# STATION_1608_v1.net
KiCad netlist of a schematic drawn in EAGLE
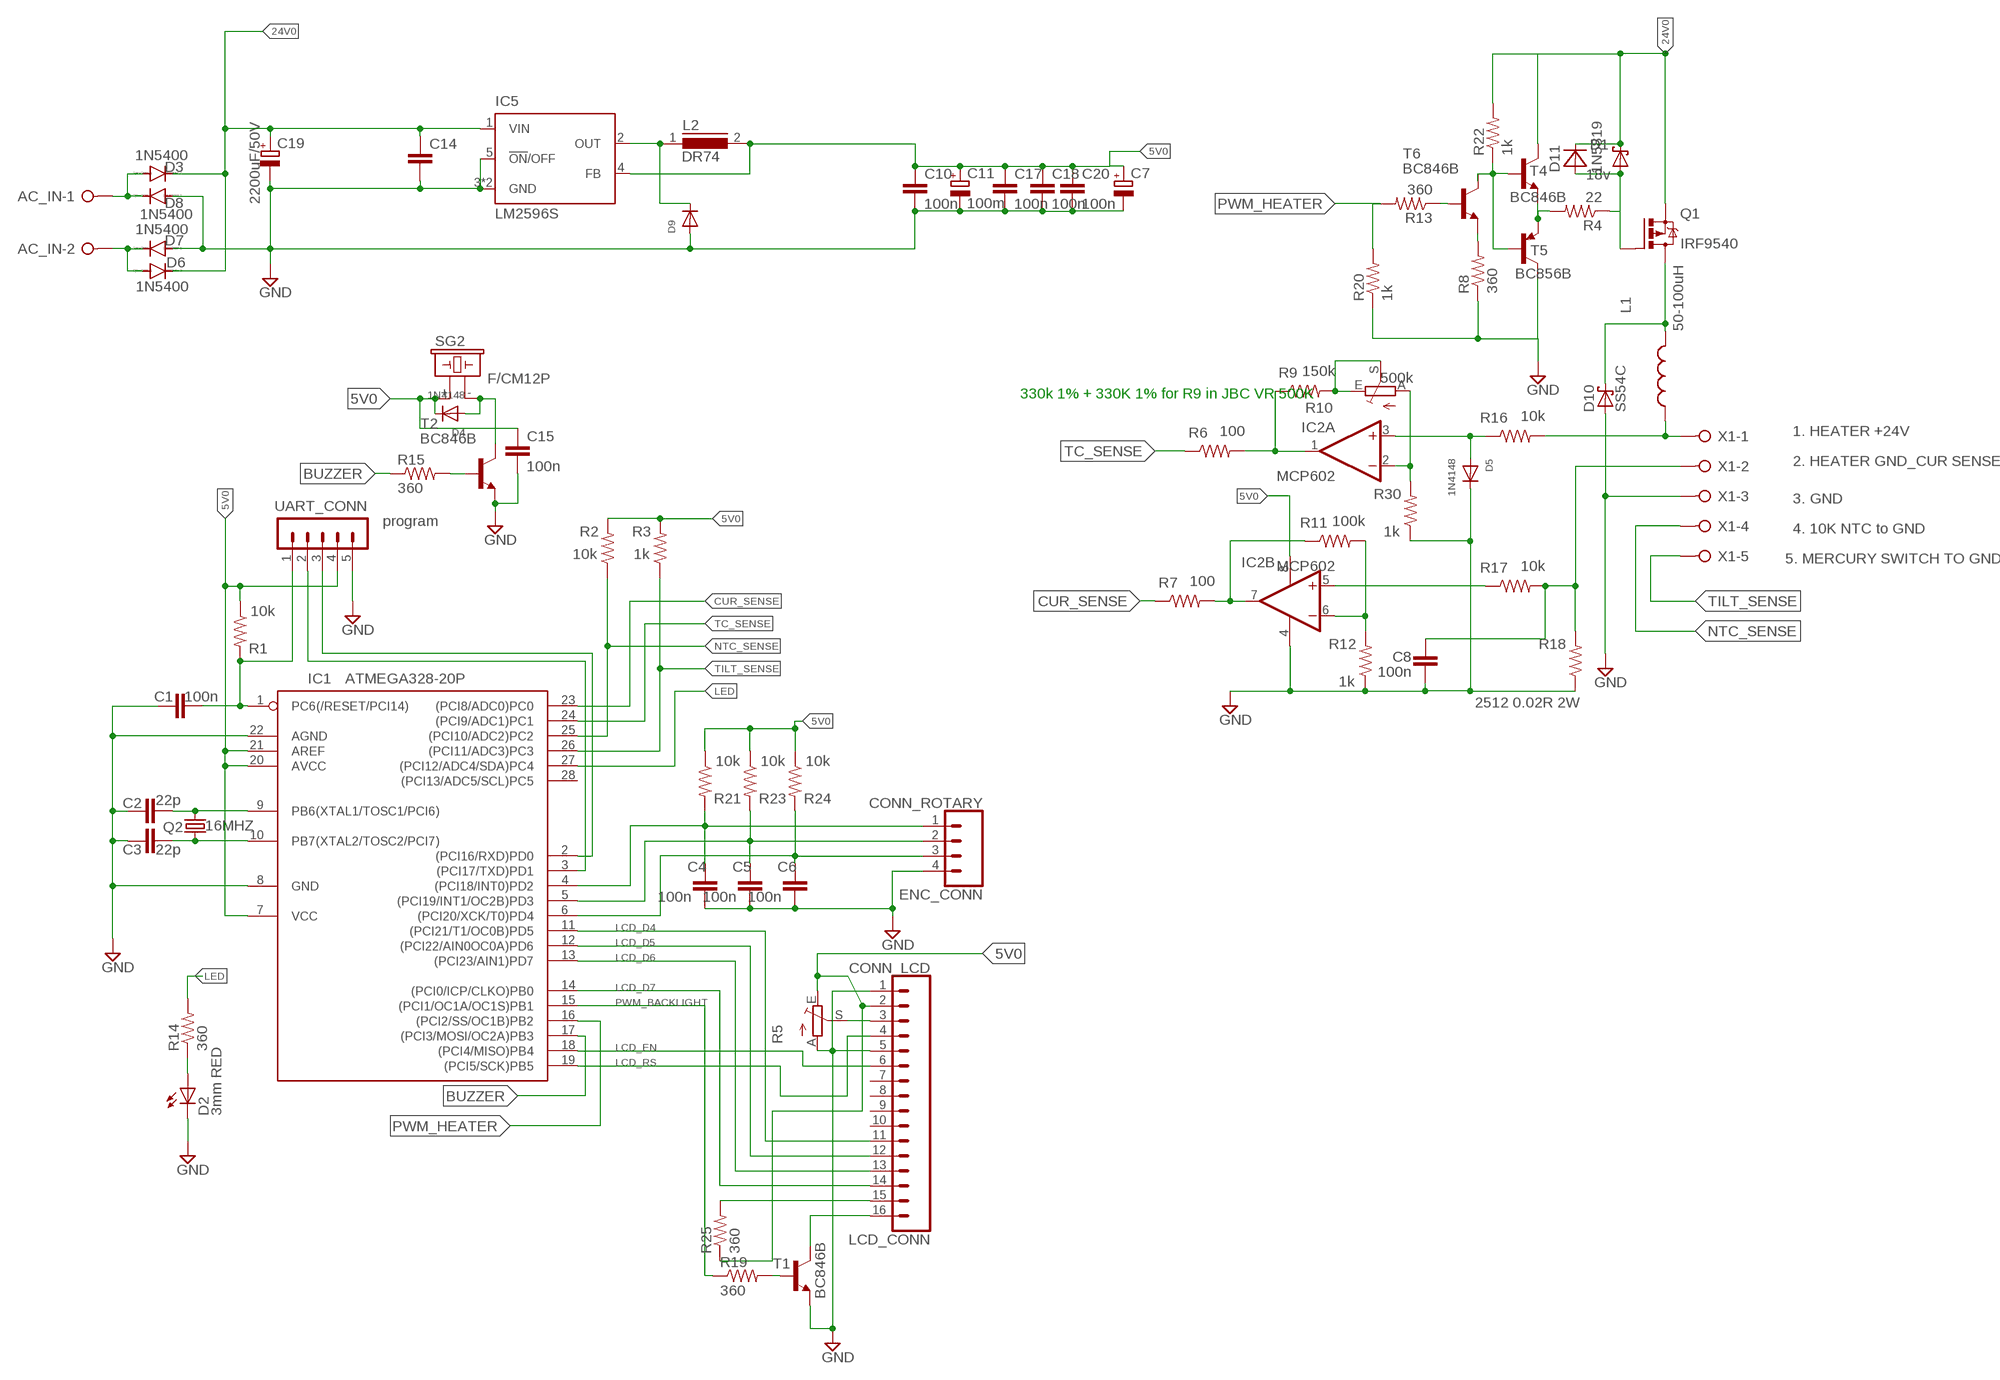
[diagram p0: schematic, sheet 1]

(export (version "E")
  (design (tool "Eeschema 10.0.6"))
  (components
    (comp (ref "AC_IN")
      (value "W237-02P")
      (footprint "eagle-import:W237-132")
      (libsource (lib "eagle-import") (part "W237-02P"))
    )
    (comp (ref "C1")
      (value "100n")
      (footprint "eagle-import:C0805")
      (libsource (lib "eagle-import") (part "C-EUC0805"))
    )
    (comp (ref "C2")
      (value "22p")
      (footprint "eagle-import:C0805")
      (libsource (lib "eagle-import") (part "C-EUC0805"))
    )
    (comp (ref "C3")
      (value "22p")
      (footprint "eagle-import:C0805")
      (libsource (lib "eagle-import") (part "C-EUC0805"))
    )
    (comp (ref "C4")
      (value "100n")
      (footprint "eagle-import:C0805")
      (libsource (lib "eagle-import") (part "C-EUC0805"))
    )
    (comp (ref "C5")
      (value "100n")
      (footprint "eagle-import:C0805")
      (libsource (lib "eagle-import") (part "C-EUC0805"))
    )
    (comp (ref "C6")
      (value "100n")
      (footprint "eagle-import:C0805")
      (libsource (lib "eagle-import") (part "C-EUC0805"))
    )
    (comp (ref "C7")
      (value "CPOL-EUE3.5-8")
      (footprint "eagle-import:E3,5-8")
      (libsource (lib "eagle-import") (part "CPOL-EUE3.5-8"))
    )
    (comp (ref "C8")
      (value "100n")
      (footprint "eagle-import:C0805")
      (libsource (lib "eagle-import") (part "C-EUC0805"))
    )
    (comp (ref "C10")
      (value "100n")
      (footprint "eagle-import:C0805")
      (libsource (lib "eagle-import") (part "resistor_C-EUC0805"))
    )
    (comp (ref "C11")
      (value "100m")
      (footprint "eagle-import:E3,5-8")
      (libsource (lib "eagle-import") (part "CPOL-EUE3.5-8"))
    )
    (comp (ref "C14")
      (value "100n")
      (footprint "eagle-import:C0805")
      (libsource (lib "eagle-import") (part "resistor_C-EUC0805"))
    )
    (comp (ref "C15")
      (value "100n")
      (footprint "eagle-import:C0805K")
      (libsource (lib "eagle-import") (part "C-EUC0805K"))
    )
    (comp (ref "C17")
      (value "100n")
      (footprint "eagle-import:C0805")
      (libsource (lib "eagle-import") (part "resistor_C-EUC0805"))
    )
    (comp (ref "C18")
      (value "100n")
      (footprint "eagle-import:C0805")
      (libsource (lib "eagle-import") (part "resistor_C-EUC0805"))
    )
    (comp (ref "C19")
      (value "2200uF/50V")
      (footprint "eagle-import:E7,5-16")
      (libsource (lib "eagle-import") (part "CPOL-EUE7.5-16"))
    )
    (comp (ref "C20")
      (value "100n")
      (footprint "eagle-import:C0805")
      (libsource (lib "eagle-import") (part "resistor_C-EUC0805"))
    )
    (comp (ref "D1")
      (value "18v")
      (footprint "eagle-import:SOD80C")
      (libsource (lib "eagle-import") (part "BAS85"))
    )
    (comp (ref "D2")
      (value "3mm RED")
      (footprint "eagle-import:LED5MM")
      (libsource (lib "eagle-import") (part "LED5MM"))
    )
    (comp (ref "D3")
      (value "1N5400")
      (footprint "eagle-import:DO201-15")
      (libsource (lib "eagle-import") (part "1N5400"))
    )
    (comp (ref "D4")
      (value "1N4148")
      (footprint "eagle-import:SOD-123")
      (libsource (lib "eagle-import") (part "DIODESOD-123"))
    )
    (comp (ref "D5")
      (value "1N4148")
      (footprint "eagle-import:SOD-123")
      (libsource (lib "eagle-import") (part "DIODESOD-123"))
    )
    (comp (ref "D6")
      (value "1N5400")
      (footprint "eagle-import:DO201-15")
      (libsource (lib "eagle-import") (part "1N5400"))
    )
    (comp (ref "D7")
      (value "1N5400")
      (footprint "eagle-import:DO201-15")
      (libsource (lib "eagle-import") (part "1N5400"))
    )
    (comp (ref "D8")
      (value "1N5400")
      (footprint "eagle-import:DO201-15")
      (libsource (lib "eagle-import") (part "1N5400"))
    )
    (comp (ref "D9")
      (value "DIODESMA")
      (footprint "eagle-import:SMADIODE")
      (libsource (lib "eagle-import") (part "DIODESMA"))
    )
    (comp (ref "D10")
      (value "SS54C")
      (footprint "eagle-import:SMC")
      (libsource (lib "eagle-import") (part "MBRS30T32"))
    )
    (comp (ref "D11")
      (value "1N5819")
      (footprint "eagle-import:SMA")
      (libsource (lib "eagle-import") (part "MBRA340T3"))
    )
    (comp (ref "ENC_CONN")
      (value "CONN_ROTARY")
      (footprint "eagle-import:1X04_LONGPADS")
      (libsource (lib "eagle-import") (part "CONN_04LONGPADS"))
    )
    (comp (ref "IC1")
      (value "ATMEGA328-20P")
      (footprint "eagle-import:DIL28-3")
      (libsource (lib "eagle-import") (part "ATMEGA328P-20"))
    )
    (comp (ref "IC2")
      (value "MCP602")
      (footprint "eagle-import:DIL08")
      (libsource (lib "eagle-import") (part "MCP602P"))
    )
    (comp (ref "IC5")
      (value "LM2596S")
      (footprint "eagle-import:TO263-5")
      (fields (field (name "MF") "NATIONAL SEMICONDUCTOR") (field (name "MPN") "LM2596S-ADJ/NOPB"))
      (libsource (lib "eagle-import") (part "LM2596S"))
    )
    (comp (ref "L1")
      (value "50-100uH")
      (footprint "eagle-import:IRF46")
      (libsource (lib "eagle-import") (part "L-USIRF-46"))
    )
    (comp (ref "L2")
      (value "DR74")
      (footprint "eagle-import:DR74")
      (libsource (lib "eagle-import") (part "DR74"))
    )
    (comp (ref "LCD_CONN")
      (value "CONN_LCD")
      (footprint "eagle-import:1X16_LONGPADS")
      (libsource (lib "eagle-import") (part "CONN_16LONGPADS"))
    )
    (comp (ref "Q1")
      (value "IRF9540")
      (footprint "eagle-import:TO220BV")
      (libsource (lib "eagle-import") (part "IRF4905FG"))
    )
    (comp (ref "Q2")
      (value "16MHZ")
      (footprint "eagle-import:HC49_S")
      (libsource (lib "eagle-import") (part "CRYSTALHC49S"))
    )
    (comp (ref "R1")
      (value "10k")
      (footprint "eagle-import:M0805")
      (libsource (lib "eagle-import") (part "R-US_M0805"))
    )
    (comp (ref "R2")
      (value "10k")
      (footprint "eagle-import:M0805")
      (libsource (lib "eagle-import") (part "R-US_M0805"))
    )
    (comp (ref "R3")
      (value "1k")
      (footprint "eagle-import:M0805")
      (libsource (lib "eagle-import") (part "R-US_M0805"))
    )
    (comp (ref "R4")
      (value "22")
      (footprint "eagle-import:M0805")
      (libsource (lib "eagle-import") (part "R-US_M0805"))
    )
    (comp (ref "R5")
      (value "TRIM_EU-RJ9W")
      (footprint "eagle-import:RJ9W")
      (libsource (lib "eagle-import") (part "TRIM_EU-RJ9W"))
    )
    (comp (ref "R6")
      (value "100")
      (footprint "eagle-import:M0805")
      (libsource (lib "eagle-import") (part "R-US_M0805"))
    )
    (comp (ref "R7")
      (value "100")
      (footprint "eagle-import:M0805")
      (libsource (lib "eagle-import") (part "R-US_M0805"))
    )
    (comp (ref "R8")
      (value "360")
      (footprint "eagle-import:M0805")
      (libsource (lib "eagle-import") (part "R-US_M0805"))
    )
    (comp (ref "R9")
      (value "150k")
      (footprint "eagle-import:M0805")
      (libsource (lib "eagle-import") (part "R-US_M0805"))
    )
    (comp (ref "R10")
      (value "500k")
      (footprint "eagle-import:RJ9W")
      (libsource (lib "eagle-import") (part "TRIM_EU-RJ9W"))
    )
    (comp (ref "R11")
      (value "100k")
      (footprint "eagle-import:M0805")
      (libsource (lib "eagle-import") (part "R-US_M0805"))
    )
    (comp (ref "R12")
      (value "1k")
      (footprint "eagle-import:M0805")
      (libsource (lib "eagle-import") (part "R-US_M0805"))
    )
    (comp (ref "R13")
      (value "360")
      (footprint "eagle-import:M0805")
      (libsource (lib "eagle-import") (part "R-US_M0805"))
    )
    (comp (ref "R14")
      (value "360")
      (footprint "eagle-import:M0805")
      (libsource (lib "eagle-import") (part "R-US_M0805"))
    )
    (comp (ref "R15")
      (value "360")
      (footprint "eagle-import:M0805")
      (libsource (lib "eagle-import") (part "R-US_M0805"))
    )
    (comp (ref "R16")
      (value "10k")
      (footprint "eagle-import:M0805")
      (libsource (lib "eagle-import") (part "R-US_M0805"))
    )
    (comp (ref "R17")
      (value "10k")
      (footprint "eagle-import:M0805")
      (libsource (lib "eagle-import") (part "R-US_M0805"))
    )
    (comp (ref "R18")
      (value "2512 0.02R 2W")
      (footprint "eagle-import:R2512")
      (libsource (lib "eagle-import") (part "R-US_R2512"))
    )
    (comp (ref "R19")
      (value "360")
      (footprint "eagle-import:M0805")
      (libsource (lib "eagle-import") (part "R-US_M0805"))
    )
    (comp (ref "R20")
      (value "1k")
      (footprint "eagle-import:M0805")
      (libsource (lib "eagle-import") (part "R-US_M0805"))
    )
    (comp (ref "R21")
      (value "10k")
      (footprint "eagle-import:M0805")
      (libsource (lib "eagle-import") (part "R-US_M0805"))
    )
    (comp (ref "R22")
      (value "1k")
      (footprint "eagle-import:M0805")
      (libsource (lib "eagle-import") (part "R-US_M0805"))
    )
    (comp (ref "R23")
      (value "10k")
      (footprint "eagle-import:M0805")
      (libsource (lib "eagle-import") (part "R-US_M0805"))
    )
    (comp (ref "R24")
      (value "10k")
      (footprint "eagle-import:M0805")
      (libsource (lib "eagle-import") (part "R-US_M0805"))
    )
    (comp (ref "R25")
      (value "360")
      (footprint "eagle-import:M0805")
      (libsource (lib "eagle-import") (part "R-US_M0805"))
    )
    (comp (ref "R30")
      (value "1k")
      (footprint "eagle-import:M0805")
      (libsource (lib "eagle-import") (part "R-US_M0805"))
    )
    (comp (ref "SG2")
      (value "F/CM12P")
      (footprint "eagle-import:F_CM12P")
      (libsource (lib "eagle-import") (part "F/CM12P"))
    )
    (comp (ref "T1")
      (value "BC846B")
      (footprint "eagle-import:SOT23-BEC")
      (libsource (lib "eagle-import") (part "-NPN-SOT23-BECBC846B"))
    )
    (comp (ref "T2")
      (value "BC846B")
      (footprint "eagle-import:SOT23-BEC")
      (libsource (lib "eagle-import") (part "-NPN-SOT23-BECBC846B"))
    )
    (comp (ref "T4")
      (value "BC846B")
      (footprint "eagle-import:SOT23-BEC")
      (libsource (lib "eagle-import") (part "-NPN-SOT23-BECBC846B"))
    )
    (comp (ref "T5")
      (value "BC856B")
      (footprint "eagle-import:SOT23-BEC")
      (libsource (lib "eagle-import") (part "-PNP-SOT23-BECBC856B"))
    )
    (comp (ref "T6")
      (value "BC846B")
      (footprint "eagle-import:SOT23-BEC")
      (libsource (lib "eagle-import") (part "-NPN-SOT23-BECBC846B"))
    )
    (comp (ref "UART_CONN")
      (value "program")
      (footprint "eagle-import:MA05-1")
      (libsource (lib "eagle-import") (part "MA05-1"))
    )
    (comp (ref "X1")
      (value "W237-05P")
      (footprint "eagle-import:W237-5P")
      (libsource (lib "eagle-import") (part "W237-05P"))
    )
  )
  (nets
    (net (code "1") (name "/LCD_D4") (class "Default")
      (node (ref "IC1") (pin "11") (pinfunction "(PCI21/T1/OC0B)PD5_11") (pintype "bidirectional"))
      (node (ref "LCD_CONN") (pin "11") (pinfunction "11_11") (pintype "passive"))
    )
    (net (code "2") (name "/LCD_D5") (class "Default")
      (node (ref "IC1") (pin "12") (pinfunction "(PCI22/AIN0OC0A)PD6_12") (pintype "bidirectional"))
      (node (ref "LCD_CONN") (pin "12") (pinfunction "12_12") (pintype "passive"))
    )
    (net (code "3") (name "/LCD_D6") (class "Default")
      (node (ref "IC1") (pin "13") (pinfunction "(PCI23/AIN1)PD7_13") (pintype "bidirectional"))
      (node (ref "LCD_CONN") (pin "13") (pinfunction "13_13") (pintype "passive"))
    )
    (net (code "4") (name "/LCD_D7") (class "Default")
      (node (ref "IC1") (pin "14") (pinfunction "(PCI0/ICP/CLKO)PB0_14") (pintype "bidirectional"))
      (node (ref "LCD_CONN") (pin "14") (pinfunction "14_14") (pintype "passive"))
    )
    (net (code "5") (name "/LCD_EN") (class "Default")
      (node (ref "IC1") (pin "18") (pinfunction "(PCI4/MISO)PB4_18") (pintype "bidirectional"))
      (node (ref "LCD_CONN") (pin "6") (pinfunction "6_6") (pintype "passive"))
    )
    (net (code "6") (name "/LCD_RS") (class "Default")
      (node (ref "IC1") (pin "19") (pinfunction "(PCI5/SCK)PB5_19") (pintype "bidirectional"))
      (node (ref "LCD_CONN") (pin "4") (pinfunction "4_4") (pintype "passive"))
    )
    (net (code "7") (name "/PWM_BACKLIGHT") (class "Default")
      (node (ref "IC1") (pin "15") (pinfunction "(PCI1/OC1A/OC1S)PB1_15") (pintype "bidirectional"))
      (node (ref "R19") (pin "1") (pinfunction "1_1") (pintype "passive"))
    )
    (net (code "8") (name "5V0") (class "Default")
      (node (ref "C10") (pin "1") (pinfunction "1_1") (pintype "passive"))
      (node (ref "C11") (pin "+") (pinfunction "+_+") (pintype "passive"))
      (node (ref "C15") (pin "1") (pinfunction "1_1") (pintype "passive"))
      (node (ref "C17") (pin "1") (pinfunction "1_1") (pintype "passive"))
      (node (ref "C18") (pin "1") (pinfunction "1_1") (pintype "passive"))
      (node (ref "C20") (pin "1") (pinfunction "1_1") (pintype "passive"))
      (node (ref "C7") (pin "+") (pinfunction "+_+") (pintype "passive"))
      (node (ref "D4") (pin "C") (pinfunction "C_C") (pintype "passive"))
      (node (ref "IC1") (pin "20") (pinfunction "AVCC_20") (pintype "bidirectional"))
      (node (ref "IC1") (pin "21") (pinfunction "AREF_21") (pintype "bidirectional"))
      (node (ref "IC1") (pin "7") (pinfunction "VCC_7") (pintype "bidirectional"))
      (node (ref "IC2") (pin "8") (pinfunction "V+_8") (pintype "power_in"))
      (node (ref "IC5") (pin "4") (pinfunction "FB_4") (pintype "input"))
      (node (ref "L2") (pin "2") (pinfunction "2_2") (pintype "passive"))
      (node (ref "LCD_CONN") (pin "2") (pinfunction "2_2") (pintype "passive"))
      (node (ref "R1") (pin "1") (pinfunction "1_1") (pintype "passive"))
      (node (ref "R2") (pin "2") (pinfunction "2_2") (pintype "passive"))
      (node (ref "R21") (pin "1") (pinfunction "1_1") (pintype "passive"))
      (node (ref "R23") (pin "1") (pinfunction "1_1") (pintype "passive"))
      (node (ref "R24") (pin "1") (pinfunction "1_1") (pintype "passive"))
      (node (ref "R25") (pin "1") (pinfunction "1_1") (pintype "passive"))
      (node (ref "R3") (pin "2") (pinfunction "2_2") (pintype "passive"))
      (node (ref "R5") (pin "E") (pinfunction "E_E") (pintype "passive"))
      (node (ref "SG2") (pin "+") (pinfunction "1_+") (pintype "passive"))
      (node (ref "UART_CONN") (pin "4") (pinfunction "4_4") (pintype "passive"))
    )
    (net (code "9") (name "24V0") (class "Default")
      (node (ref "C14") (pin "1") (pinfunction "1_1") (pintype "passive"))
      (node (ref "C19") (pin "+") (pinfunction "+_+") (pintype "passive"))
      (node (ref "D1") (pin "1") (pinfunction "K_1") (pintype "passive"))
      (node (ref "D11") (pin "C") (pinfunction "C_C") (pintype "passive"))
      (node (ref "D3") (pin "C") (pinfunction "C_C") (pintype "passive"))
      (node (ref "D6") (pin "C") (pinfunction "C_C") (pintype "passive"))
      (node (ref "IC5") (pin "1") (pinfunction "VIN_1") (pintype "input"))
      (node (ref "Q1") (pin "S") (pinfunction "S_S") (pintype "passive"))
      (node (ref "R22") (pin "2") (pinfunction "2_2") (pintype "passive"))
      (node (ref "T4") (pin "C") (pinfunction "C_C") (pintype "passive"))
    )
    (net (code "10") (name "BUZZER") (class "Default")
      (node (ref "IC1") (pin "17") (pinfunction "(PCI3/MOSI/OC2A)PB3_17") (pintype "bidirectional"))
      (node (ref "R15") (pin "1") (pinfunction "1_1") (pintype "passive"))
    )
    (net (code "11") (name "CUR_SENSE") (class "Default")
      (node (ref "IC1") (pin "23") (pinfunction "(PCI8/ADC0)PC0_23") (pintype "bidirectional"))
      (node (ref "R7") (pin "1") (pinfunction "1_1") (pintype "passive"))
    )
    (net (code "12") (name "GND") (class "Default")
      (node (ref "C1") (pin "1") (pinfunction "1_1") (pintype "passive"))
      (node (ref "C10") (pin "2") (pinfunction "2_2") (pintype "passive"))
      (node (ref "C11") (pin "-") (pinfunction "-_-") (pintype "passive"))
      (node (ref "C14") (pin "2") (pinfunction "2_2") (pintype "passive"))
      (node (ref "C15") (pin "2") (pinfunction "2_2") (pintype "passive"))
      (node (ref "C17") (pin "2") (pinfunction "2_2") (pintype "passive"))
      (node (ref "C18") (pin "2") (pinfunction "2_2") (pintype "passive"))
      (node (ref "C19") (pin "-") (pinfunction "-_-") (pintype "passive"))
      (node (ref "C2") (pin "1") (pinfunction "1_1") (pintype "passive"))
      (node (ref "C20") (pin "2") (pinfunction "2_2") (pintype "passive"))
      (node (ref "C3") (pin "1") (pinfunction "1_1") (pintype "passive"))
      (node (ref "C4") (pin "2") (pinfunction "2_2") (pintype "passive"))
      (node (ref "C5") (pin "2") (pinfunction "2_2") (pintype "passive"))
      (node (ref "C6") (pin "2") (pinfunction "2_2") (pintype "passive"))
      (node (ref "C7") (pin "-") (pinfunction "-_-") (pintype "passive"))
      (node (ref "C8") (pin "2") (pinfunction "2_2") (pintype "passive"))
      (node (ref "D10") (pin "A") (pinfunction "A_A") (pintype "passive"))
      (node (ref "D2") (pin "K") (pinfunction "C_K") (pintype "passive"))
      (node (ref "D5") (pin "C") (pinfunction "C_C") (pintype "passive"))
      (node (ref "D7") (pin "A") (pinfunction "A_A") (pintype "passive"))
      (node (ref "D8") (pin "A") (pinfunction "A_A") (pintype "passive"))
      (node (ref "D9") (pin "A") (pinfunction "A_A") (pintype "passive"))
      (node (ref "ENC_CONN") (pin "4") (pinfunction "4_4") (pintype "passive"))
      (node (ref "IC1") (pin "22") (pinfunction "AGND_22") (pintype "bidirectional"))
      (node (ref "IC1") (pin "8") (pinfunction "GND_8") (pintype "bidirectional"))
      (node (ref "IC2") (pin "4") (pinfunction "V-_4") (pintype "power_in"))
      (node (ref "IC5") (pin "3") (pinfunction "GND_3") (pintype "power_in"))
      (node (ref "IC5") (pin "5") (pinfunction "~{ON}/OFF_5") (pintype "input"))
      (node (ref "IC5") (pin "6") (pinfunction "GND_6") (pintype "power_in"))
      (node (ref "LCD_CONN") (pin "1") (pinfunction "1_1") (pintype "passive"))
      (node (ref "LCD_CONN") (pin "5") (pinfunction "5_5") (pintype "passive"))
      (node (ref "R12") (pin "1") (pinfunction "1_1") (pintype "passive"))
      (node (ref "R18") (pin "1") (pinfunction "1_1") (pintype "passive"))
      (node (ref "R20") (pin "1") (pinfunction "1_1") (pintype "passive"))
      (node (ref "R30") (pin "1") (pinfunction "1_1") (pintype "passive"))
      (node (ref "R5") (pin "A") (pinfunction "A_A") (pintype "passive"))
      (node (ref "R8") (pin "1") (pinfunction "1_1") (pintype "passive"))
      (node (ref "T1") (pin "E") (pinfunction "E_E") (pintype "passive"))
      (node (ref "T2") (pin "E") (pinfunction "E_E") (pintype "passive"))
      (node (ref "T5") (pin "C") (pinfunction "C_C") (pintype "passive"))
      (node (ref "UART_CONN") (pin "5") (pinfunction "5_5") (pintype "passive"))
      (node (ref "X1") (pin "3") (pinfunction "KL_3") (pintype "passive"))
    )
    (net (code "13") (name "LED") (class "Default")
      (node (ref "IC1") (pin "27") (pinfunction "(PCI12/ADC4/SDA)PC4_27") (pintype "bidirectional"))
      (node (ref "R14") (pin "2") (pinfunction "2_2") (pintype "passive"))
    )
    (net (code "14") (name "NTC_SENSE") (class "Default")
      (node (ref "IC1") (pin "25") (pinfunction "(PCI10/ADC2)PC2_25") (pintype "bidirectional"))
      (node (ref "R2") (pin "1") (pinfunction "1_1") (pintype "passive"))
      (node (ref "X1") (pin "4") (pinfunction "KL_4") (pintype "passive"))
    )
    (net (code "15") (name "Net-(AC_INA-KL)") (class "Default")
      (node (ref "AC_IN") (pin "1") (pinfunction "KL_1") (pintype "passive"))
      (node (ref "D3") (pin "A") (pinfunction "A_A") (pintype "passive"))
      (node (ref "D8") (pin "C") (pinfunction "C_C") (pintype "passive"))
    )
    (net (code "16") (name "Net-(AC_INB-KL)") (class "Default")
      (node (ref "AC_IN") (pin "2") (pinfunction "KL_2") (pintype "passive"))
      (node (ref "D6") (pin "A") (pinfunction "A_A") (pintype "passive"))
      (node (ref "D7") (pin "C") (pinfunction "C_C") (pintype "passive"))
    )
    (net (code "17") (name "Net-(D1-A)") (class "Default")
      (node (ref "D1") (pin "2") (pinfunction "A_2") (pintype "passive"))
      (node (ref "D11") (pin "A") (pinfunction "A_A") (pintype "passive"))
      (node (ref "Q1") (pin "G") (pinfunction "G_G") (pintype "passive"))
      (node (ref "R4") (pin "1") (pinfunction "1_1") (pintype "passive"))
    )
    (net (code "18") (name "Net-(D2-PadA)") (class "Default")
      (node (ref "D2") (pin "A") (pinfunction "A_A") (pintype "passive"))
      (node (ref "R14") (pin "1") (pinfunction "1_1") (pintype "passive"))
    )
    (net (code "19") (name "Net-(D10-PadC)") (class "Default")
      (node (ref "D10") (pin "C") (pinfunction "C_C") (pintype "passive"))
      (node (ref "L1") (pin "2") (pinfunction "2_2") (pintype "passive"))
      (node (ref "Q1") (pin "D") (pinfunction "D_D") (pintype "passive"))
    )
    (net (code "20") (name "Net-(IC1-(PCI16{slash}RXD)PD0)") (class "Default")
      (node (ref "IC1") (pin "2") (pinfunction "(PCI16/RXD)PD0_2") (pintype "bidirectional"))
      (node (ref "UART_CONN") (pin "3") (pinfunction "3_3") (pintype "passive"))
    )
    (net (code "21") (name "Net-(IC1-(PCI17{slash}TXD)PD1)") (class "Default")
      (node (ref "IC1") (pin "3") (pinfunction "(PCI17/TXD)PD1_3") (pintype "bidirectional"))
      (node (ref "UART_CONN") (pin "2") (pinfunction "2_2") (pintype "passive"))
    )
    (net (code "22") (name "Net-(IC1-(PCI18{slash}INT0)PD2)") (class "Default")
      (node (ref "C4") (pin "1") (pinfunction "1_1") (pintype "passive"))
      (node (ref "ENC_CONN") (pin "1") (pinfunction "1_1") (pintype "passive"))
      (node (ref "IC1") (pin "4") (pinfunction "(PCI18/INT0)PD2_4") (pintype "bidirectional"))
      (node (ref "R21") (pin "2") (pinfunction "2_2") (pintype "passive"))
    )
    (net (code "23") (name "Net-(IC1-(PCI19{slash}INT1{slash}OC2B)PD3)") (class "Default")
      (node (ref "C5") (pin "1") (pinfunction "1_1") (pintype "passive"))
      (node (ref "ENC_CONN") (pin "2") (pinfunction "2_2") (pintype "passive"))
      (node (ref "IC1") (pin "5") (pinfunction "(PCI19/INT1/OC2B)PD3_5") (pintype "bidirectional"))
      (node (ref "R23") (pin "2") (pinfunction "2_2") (pintype "passive"))
    )
    (net (code "24") (name "Net-(IC1-(PCI20{slash}XCK{slash}T0)PD4)") (class "Default")
      (node (ref "C6") (pin "1") (pinfunction "1_1") (pintype "passive"))
      (node (ref "ENC_CONN") (pin "3") (pinfunction "3_3") (pintype "passive"))
      (node (ref "IC1") (pin "6") (pinfunction "(PCI20/XCK/T0)PD4_6") (pintype "bidirectional"))
      (node (ref "R24") (pin "2") (pinfunction "2_2") (pintype "passive"))
    )
    (net (code "25") (name "Net-(IC1-PB6(XTAL1{slash}TOSC1{slash}PCI6))") (class "Default")
      (node (ref "C2") (pin "2") (pinfunction "2_2") (pintype "passive"))
      (node (ref "IC1") (pin "9") (pinfunction "PB6(XTAL1/TOSC1/PCI6)_9") (pintype "bidirectional"))
      (node (ref "Q2") (pin "2") (pinfunction "2_2") (pintype "passive"))
    )
    (net (code "26") (name "Net-(IC1-PB7(XTAL2{slash}TOSC2{slash}PCI7))") (class "Default")
      (node (ref "C3") (pin "2") (pinfunction "2_2") (pintype "passive"))
      (node (ref "IC1") (pin "10") (pinfunction "PB7(XTAL2/TOSC2/PCI7)_10") (pintype "bidirectional"))
      (node (ref "Q2") (pin "1") (pinfunction "1_1") (pintype "passive"))
    )
    (net (code "27") (name "Net-(IC1-PC6({slash}RESET{slash}PCI14))") (class "Default")
      (node (ref "C1") (pin "2") (pinfunction "2_2") (pintype "passive"))
      (node (ref "IC1") (pin "1") (pinfunction "PC6(/RESET/PCI14)_1") (pintype "bidirectional"))
      (node (ref "R1") (pin "2") (pinfunction "2_2") (pintype "passive"))
      (node (ref "UART_CONN") (pin "1") (pinfunction "1_1") (pintype "passive"))
    )
    (net (code "28") (name "Net-(IC2A-+IN)") (class "Default")
      (node (ref "D5") (pin "A") (pinfunction "A_A") (pintype "passive"))
      (node (ref "IC2") (pin "3") (pinfunction "+IN_3") (pintype "input"))
      (node (ref "R16") (pin "1") (pinfunction "1_1") (pintype "passive"))
    )
    (net (code "29") (name "Net-(IC2A--IN)") (class "Default")
      (node (ref "IC2") (pin "2") (pinfunction "-IN_2") (pintype "input"))
      (node (ref "R10") (pin "A") (pinfunction "A_A") (pintype "passive"))
      (node (ref "R30") (pin "2") (pinfunction "2_2") (pintype "passive"))
    )
    (net (code "30") (name "Net-(IC2A-OUT)") (class "Default")
      (node (ref "IC2") (pin "1") (pinfunction "OUT_1") (pintype "output"))
      (node (ref "R6") (pin "2") (pinfunction "2_2") (pintype "passive"))
      (node (ref "R9") (pin "1") (pinfunction "1_1") (pintype "passive"))
    )
    (net (code "31") (name "Net-(IC2B-+IN)") (class "Default")
      (node (ref "IC2") (pin "5") (pinfunction "+IN_5") (pintype "input"))
      (node (ref "R17") (pin "1") (pinfunction "1_1") (pintype "passive"))
    )
    (net (code "32") (name "Net-(IC2B--IN)") (class "Default")
      (node (ref "IC2") (pin "6") (pinfunction "-IN_6") (pintype "input"))
      (node (ref "R11") (pin "2") (pinfunction "2_2") (pintype "passive"))
      (node (ref "R12") (pin "2") (pinfunction "2_2") (pintype "passive"))
    )
    (net (code "33") (name "Net-(IC2B-OUT)") (class "Default")
      (node (ref "IC2") (pin "7") (pinfunction "OUT_7") (pintype "output"))
      (node (ref "R11") (pin "1") (pinfunction "1_1") (pintype "passive"))
      (node (ref "R7") (pin "2") (pinfunction "2_2") (pintype "passive"))
    )
    (net (code "34") (name "Net-(IC5-OUT)") (class "Default")
      (node (ref "D9") (pin "C") (pinfunction "C_C") (pintype "passive"))
      (node (ref "IC5") (pin "2") (pinfunction "OUT_2") (pintype "output"))
      (node (ref "L2") (pin "1") (pinfunction "1_1") (pintype "passive"))
    )
    (net (code "35") (name "Net-(LCD_CONN-Pad3)") (class "Default")
      (node (ref "LCD_CONN") (pin "3") (pinfunction "3_3") (pintype "passive"))
      (node (ref "R5") (pin "S") (pinfunction "S_S") (pintype "passive"))
    )
    (net (code "36") (name "Net-(LCD_CONN-Pad15)") (class "Default")
      (node (ref "LCD_CONN") (pin "15") (pinfunction "15_15") (pintype "passive"))
      (node (ref "R25") (pin "2") (pinfunction "2_2") (pintype "passive"))
    )
    (net (code "37") (name "Net-(LCD_CONN-Pad16)") (class "Default")
      (node (ref "LCD_CONN") (pin "16") (pinfunction "16_16") (pintype "passive"))
      (node (ref "T1") (pin "C") (pinfunction "C_C") (pintype "passive"))
    )
    (net (code "38") (name "Net-(R4-Pad2)") (class "Default")
      (node (ref "R4") (pin "2") (pinfunction "2_2") (pintype "passive"))
      (node (ref "T4") (pin "E") (pinfunction "E_E") (pintype "passive"))
      (node (ref "T5") (pin "E") (pinfunction "E_E") (pintype "passive"))
    )
    (net (code "39") (name "Net-(R8-Pad2)") (class "Default")
      (node (ref "R8") (pin "2") (pinfunction "2_2") (pintype "passive"))
      (node (ref "T6") (pin "E") (pinfunction "E_E") (pintype "passive"))
    )
    (net (code "40") (name "Net-(R10-PadE)") (class "Default")
      (node (ref "R10") (pin "E") (pinfunction "E_E") (pintype "passive"))
      (node (ref "R10") (pin "S") (pinfunction "S_S") (pintype "passive"))
      (node (ref "R9") (pin "2") (pinfunction "2_2") (pintype "passive"))
    )
    (net (code "41") (name "Net-(R13-Pad1)") (class "Default")
      (node (ref "R13") (pin "1") (pinfunction "1_1") (pintype "passive"))
      (node (ref "T6") (pin "B") (pinfunction "B_B") (pintype "passive"))
    )
    (net (code "42") (name "Net-(R15-Pad2)") (class "Default")
      (node (ref "R15") (pin "2") (pinfunction "2_2") (pintype "passive"))
      (node (ref "T2") (pin "B") (pinfunction "B_B") (pintype "passive"))
    )
    (net (code "43") (name "Net-(R19-Pad2)") (class "Default")
      (node (ref "R19") (pin "2") (pinfunction "2_2") (pintype "passive"))
      (node (ref "T1") (pin "B") (pinfunction "B_B") (pintype "passive"))
    )
    (net (code "44") (name "Net-(R22-Pad1)") (class "Default")
      (node (ref "R22") (pin "1") (pinfunction "1_1") (pintype "passive"))
      (node (ref "T4") (pin "B") (pinfunction "B_B") (pintype "passive"))
      (node (ref "T5") (pin "B") (pinfunction "B_B") (pintype "passive"))
      (node (ref "T6") (pin "C") (pinfunction "C_C") (pintype "passive"))
    )
    (net (code "45") (name "Net-(SG2-2)") (class "Default")
      (node (ref "D4") (pin "A") (pinfunction "A_A") (pintype "passive"))
      (node (ref "SG2") (pin "-") (pinfunction "2_-") (pintype "passive"))
      (node (ref "T2") (pin "C") (pinfunction "C_C") (pintype "passive"))
    )
    (net (code "46") (name "Net-(X1A-KL)") (class "Default")
      (node (ref "L1") (pin "1") (pinfunction "1_1") (pintype "passive"))
      (node (ref "R16") (pin "2") (pinfunction "2_2") (pintype "passive"))
      (node (ref "X1") (pin "1") (pinfunction "KL_1") (pintype "passive"))
    )
    (net (code "47") (name "Net-(X1B-KL)") (class "Default")
      (node (ref "C8") (pin "1") (pinfunction "1_1") (pintype "passive"))
      (node (ref "R17") (pin "2") (pinfunction "2_2") (pintype "passive"))
      (node (ref "R18") (pin "2") (pinfunction "2_2") (pintype "passive"))
      (node (ref "X1") (pin "2") (pinfunction "KL_2") (pintype "passive"))
    )
    (net (code "48") (name "PWM_HEATER") (class "Default")
      (node (ref "IC1") (pin "16") (pinfunction "(PCI2/SS/OC1B)PB2_16") (pintype "bidirectional"))
      (node (ref "R13") (pin "2") (pinfunction "2_2") (pintype "passive"))
      (node (ref "R20") (pin "2") (pinfunction "2_2") (pintype "passive"))
    )
    (net (code "49") (name "TC_SENSE") (class "Default")
      (node (ref "IC1") (pin "24") (pinfunction "(PCI9/ADC1)PC1_24") (pintype "bidirectional"))
      (node (ref "R6") (pin "1") (pinfunction "1_1") (pintype "passive"))
    )
    (net (code "50") (name "TILT_SENSE") (class "Default")
      (node (ref "IC1") (pin "26") (pinfunction "(PCI11/ADC3)PC3_26") (pintype "bidirectional"))
      (node (ref "R3") (pin "1") (pinfunction "1_1") (pintype "passive"))
      (node (ref "X1") (pin "5") (pinfunction "KL_5") (pintype "passive"))
    )
    (net (code "51") (name "unconnected-(IC1-(PCI13{slash}ADC5{slash}SCL)PC5-Pad28)") (class "Default")
      (node (ref "IC1") (pin "28") (pinfunction "(PCI13/ADC5/SCL)PC5_28") (pintype "bidirectional"))
    )
    (net (code "52") (name "unconnected-(LCD_CONN-Pad7)") (class "Default")
      (node (ref "LCD_CONN") (pin "7") (pinfunction "7_7") (pintype "passive"))
    )
    (net (code "53") (name "unconnected-(LCD_CONN-Pad8)") (class "Default")
      (node (ref "LCD_CONN") (pin "8") (pinfunction "8_8") (pintype "passive"))
    )
    (net (code "54") (name "unconnected-(LCD_CONN-Pad9)") (class "Default")
      (node (ref "LCD_CONN") (pin "9") (pinfunction "9_9") (pintype "passive"))
    )
    (net (code "55") (name "unconnected-(LCD_CONN-Pad10)") (class "Default")
      (node (ref "LCD_CONN") (pin "10") (pinfunction "10_10") (pintype "passive"))
    )
  )
)
